# 2074.net
KiCad netlist of a schematic drawn in Altium Designer
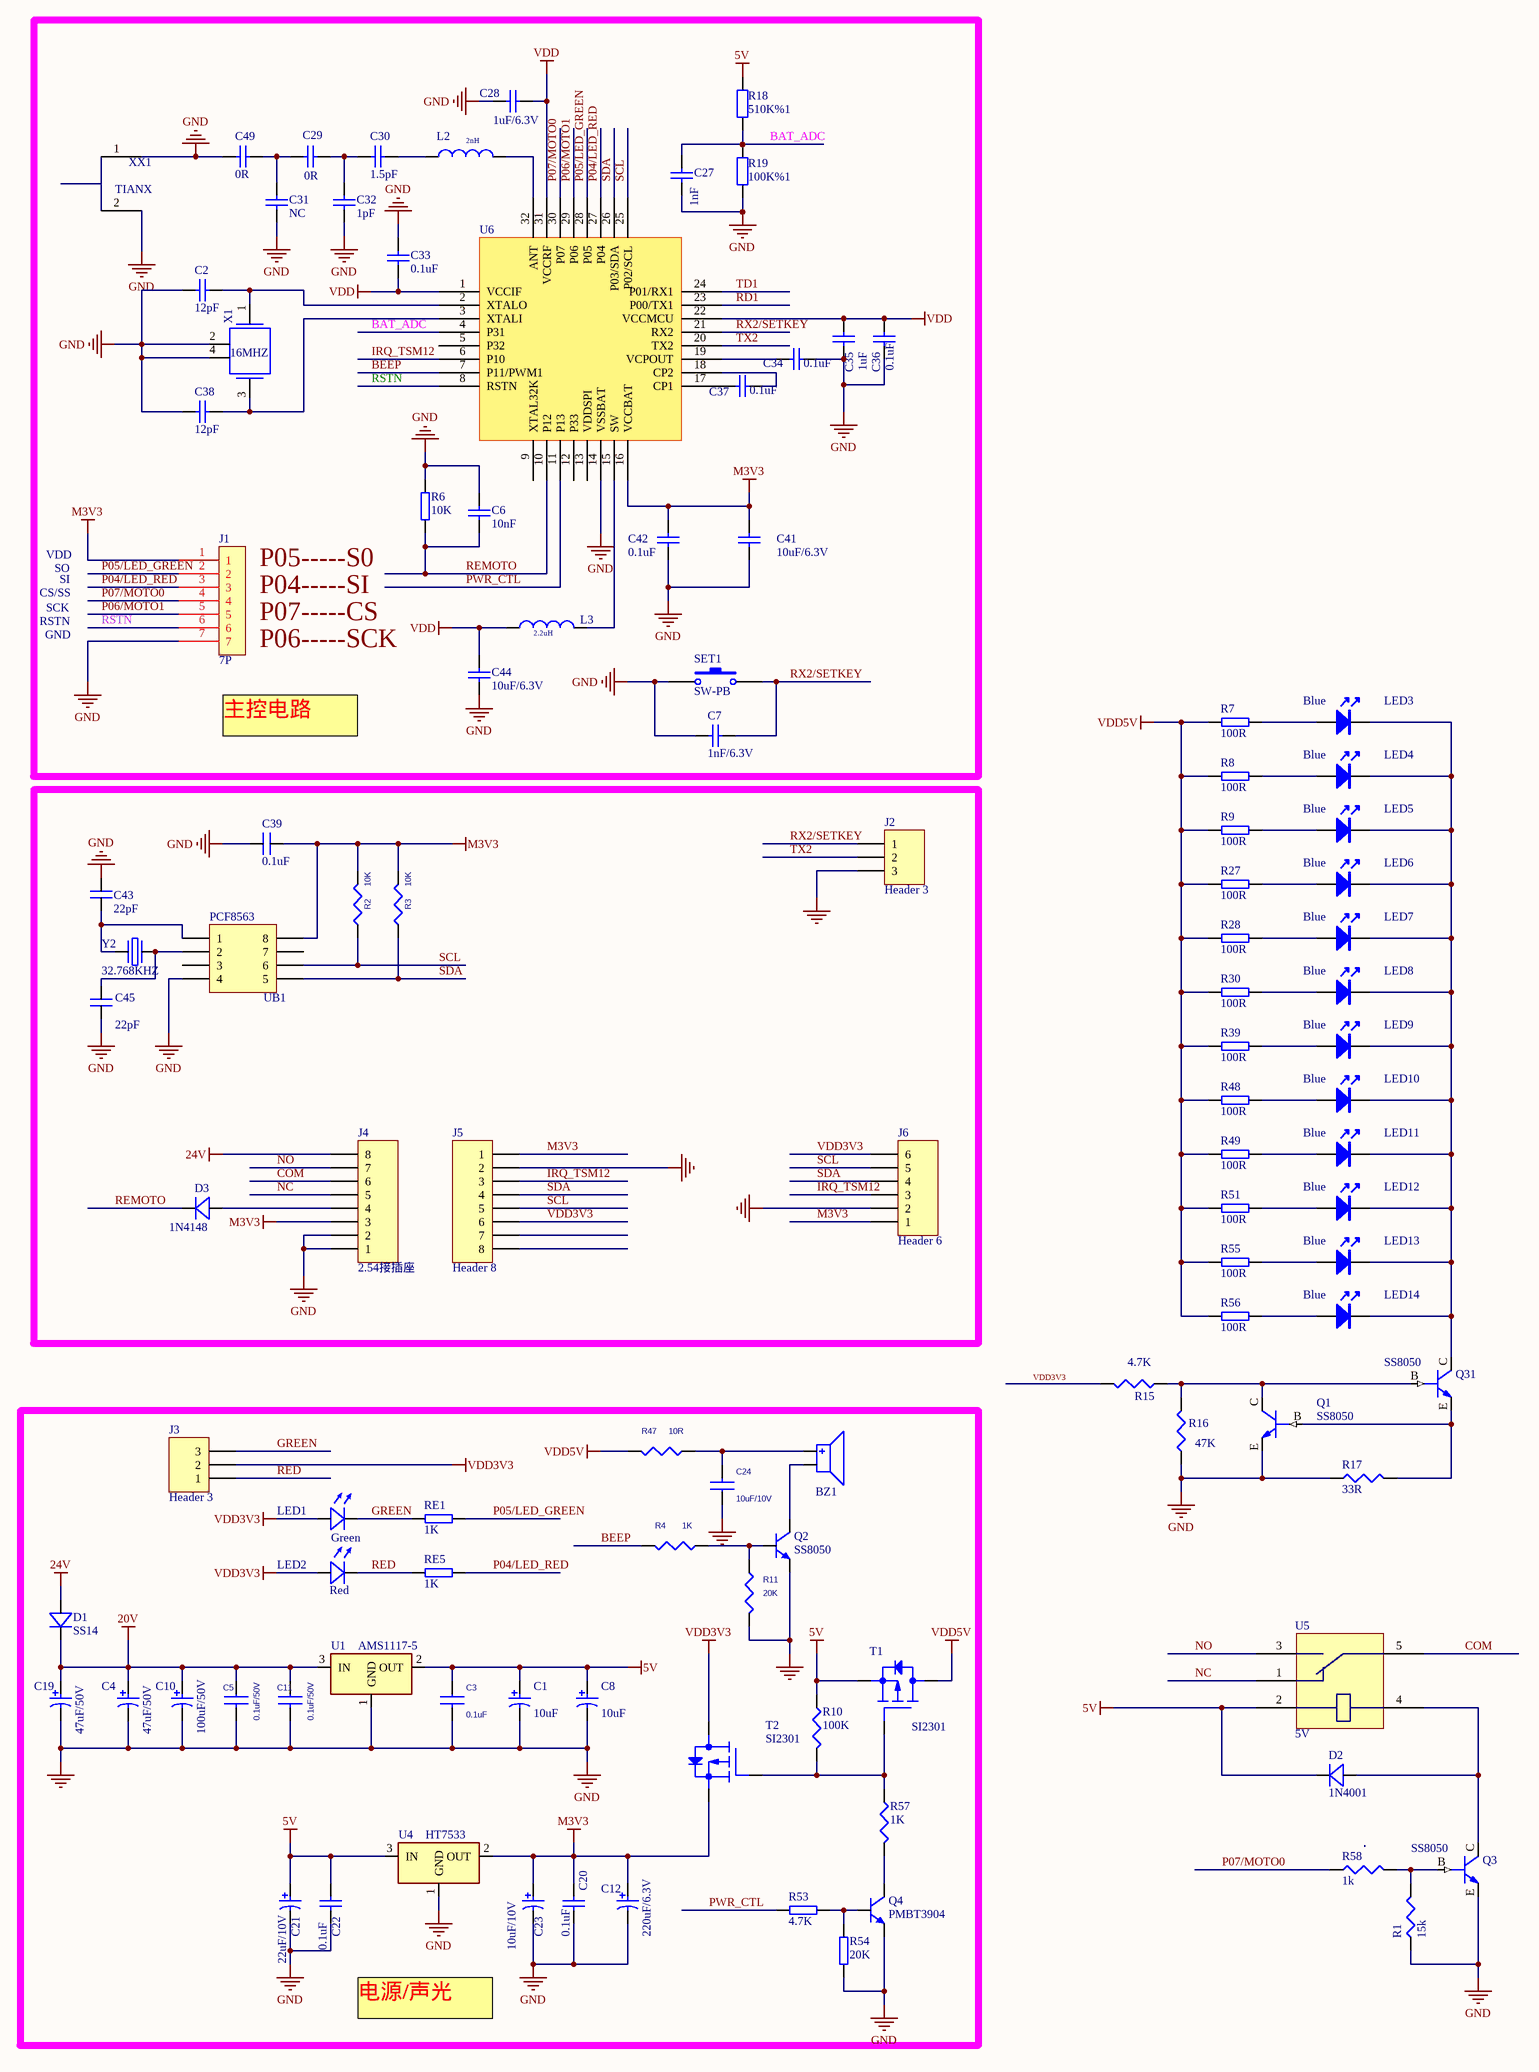
[diagram p0: 天地通门禁2074.SchDoc]

(export (version "E")
  (design (tool "Eeschema 10.0.6"))
  (components
    (comp (ref "BZ1")
      (value "BUZZER")
      (footprint "BUZZ_EN")
      (description "Buzzer")
      (libsource (lib "MyLibrary") (part "BUZZER"))
    )
    (comp (ref "C1")
      (value "10uF")
      (footprint "R6.3*5.8")
      (description "Capacitor, tolerance ±20%")
      (libsource (lib "MySchLib") (part "CAP-P"))
    )
    (comp (ref "C2")
      (value "12pF")
      (footprint "0603C")
      (description "Capacitor")
      (fields (field (name "PUBLISHER") "Altium Limited"))
      (libsource (lib "MySchlib") (part "Cap"))
    )
    (comp (ref "C3") (value "0.1uF") (footprint "0603C") (libsource (lib "*") (part "CAP NP")))
    (comp (ref "C4")
      (value "47uF/50V")
      (footprint "R6.3*7.7")
      (description "Capacitor, tolerance ±20%")
      (libsource (lib "MySchLib") (part "CAP-P"))
    )
    (comp (ref "C5") (value "0.1uF/50V") (footprint "0805C") (libsource (lib "*") (part "CAP NP")))
    (comp (ref "C6")
      (value "10nF")
      (footprint "0603C")
      (description "Capacitor")
      (fields (field (name "PUBLISHER") "Altium Limited"))
      (libsource (lib "MySchlib") (part "Cap"))
    )
    (comp (ref "C7")
      (value "1nF/6.3V")
      (footprint "0603C")
      (description "Capacitor")
      (fields (field (name "PUBLISHER") "Altium Limited"))
      (libsource (lib "MySchlib") (part "Cap"))
    )
    (comp (ref "C8")
      (value "10uF")
      (footprint "0805C")
      (description "Capacitor, tolerance ±20%")
      (libsource (lib "MySchLib") (part "CAP-P"))
    )
    (comp (ref "C10")
      (value "100uF/50V")
      (footprint "R6.3*7.7")
      (description "Capacitor, tolerance ±20%")
      (libsource (lib "MySchLib") (part "CAP-P"))
    )
    (comp (ref "C11") (value "0.1uF/50V") (footprint "0805C") (libsource (lib "*") (part "CAP NP")))
    (comp (ref "C12")
      (value "220uF/6.3V")
      (footprint "R6.3*5.8")
      (description "Capacitor, tolerance ±20%")
      (libsource (lib "MySchLib") (part "CAP-P"))
    )
    (comp (ref "C19")
      (value "47uF/50V")
      (footprint "R6.3*7.7")
      (description "Capacitor, tolerance ±20%")
      (libsource (lib "MySchLib") (part "CAP-P"))
    )
    (comp (ref "C20")
      (value "0.1uF")
      (footprint "0603C")
      (description "Capacitor, Ceramic")
      (fields (field (name "TOLERANCE") "5 %"))
      (libsource (lib "MyLibrary") (part "CAP-NP"))
    )
    (comp (ref "C21")
      (value "22uF/10V")
      (footprint "0805C")
      (description "Capacitor, tolerance ±20%")
      (libsource (lib "MySchLib") (part "CAP-P"))
    )
    (comp (ref "C22")
      (value "0.1uF")
      (footprint "0603C")
      (description "Capacitor, Ceramic")
      (fields (field (name "TOLERANCE") "5 %"))
      (libsource (lib "MyLibrary") (part "CAP-NP"))
    )
    (comp (ref "C23")
      (value "10uF/10V")
      (footprint "0805C")
      (description "Capacitor, tolerance ±20%")
      (libsource (lib "MySchLib") (part "CAP-P"))
    )
    (comp (ref "C24") (value "10uF/10V") (footprint "0805C") (libsource (lib "*") (part "C_0_Dup1")))
    (comp (ref "C27")
      (value "1nF")
      (footprint "0603C")
      (description "Capacitor, Ceramic")
      (fields (field (name "TOLERANCE") "5 %"))
      (libsource (lib "MyLibrary") (part "CAP-NP"))
    )
    (comp (ref "C28")
      (value "1uF/6.3V")
      (footprint "0603C")
      (description "Capacitor")
      (fields (field (name "PUBLISHER") "Altium Limited"))
      (libsource (lib "MySchlib") (part "Cap"))
    )
    (comp (ref "C29")
      (value "0R")
      (footprint "0603C")
      (description "Capacitor")
      (fields (field (name "PUBLISHER") "Altium Limited"))
      (libsource (lib "MySchlib") (part "Cap"))
    )
    (comp (ref "C30")
      (value "1.5pF")
      (footprint "0603C")
      (description "Capacitor")
      (fields (field (name "PUBLISHER") "Altium Limited"))
      (libsource (lib "MySchlib") (part "Cap"))
    )
    (comp (ref "C31")
      (value "NC")
      (footprint "0603C")
      (description "Capacitor")
      (fields (field (name "PUBLISHER") "Altium Limited"))
      (libsource (lib "MySchlib") (part "Cap"))
    )
    (comp (ref "C32")
      (value "1pF")
      (footprint "0603C")
      (description "Capacitor")
      (fields (field (name "PUBLISHER") "Altium Limited"))
      (libsource (lib "MySchlib") (part "Cap"))
    )
    (comp (ref "C33")
      (value "0.1uF")
      (footprint "0603C")
      (description "Capacitor")
      (fields (field (name "PUBLISHER") "Altium Limited"))
      (libsource (lib "MySchlib") (part "Cap"))
    )
    (comp (ref "C34")
      (value "0.1uF")
      (footprint "0603C")
      (description "Capacitor")
      (fields (field (name "PUBLISHER") "Altium Limited"))
      (libsource (lib "MySchlib") (part "Cap"))
    )
    (comp (ref "C35")
      (value "1uF")
      (footprint "0603C")
      (description "Capacitor")
      (fields (field (name "PUBLISHER") "Altium Limited"))
      (libsource (lib "MySchlib") (part "Cap"))
    )
    (comp (ref "C36")
      (value "0.1uF")
      (footprint "0603C")
      (description "Capacitor")
      (fields (field (name "PUBLISHER") "Altium Limited"))
      (libsource (lib "MySchlib") (part "Cap"))
    )
    (comp (ref "C37")
      (value "0.1uF")
      (footprint "0603C")
      (description "Capacitor")
      (fields (field (name "PUBLISHER") "Altium Limited"))
      (libsource (lib "MySchlib") (part "Cap"))
    )
    (comp (ref "C38")
      (value "12pF")
      (footprint "0603C")
      (description "Capacitor")
      (fields (field (name "PUBLISHER") "Altium Limited"))
      (libsource (lib "MySchlib") (part "Cap"))
    )
    (comp (ref "C39") (value "0.1uF") (footprint "0603C") (libsource (lib "自建元件库") (part "C")))
    (comp (ref "C41")
      (value "10uF/6.3V")
      (footprint "0603C")
      (description "Capacitor")
      (fields (field (name "PUBLISHER") "Altium Limited"))
      (libsource (lib "MySchlib") (part "Cap"))
    )
    (comp (ref "C42")
      (value "0.1uF")
      (footprint "0603C")
      (description "Capacitor")
      (fields (field (name "PUBLISHER") "Altium Limited"))
      (libsource (lib "MySchlib") (part "Cap"))
    )
    (comp (ref "C43") (value "22pF") (footprint "0603C") (libsource (lib "自建元件库") (part "C")))
    (comp (ref "C44")
      (value "10uF/6.3V")
      (footprint "0603C")
      (description "Capacitor")
      (fields (field (name "PUBLISHER") "Altium Limited"))
      (libsource (lib "MySchlib") (part "Cap"))
    )
    (comp (ref "C45") (value "22pF") (footprint "0603C") (libsource (lib "自建元件库") (part "C")))
    (comp (ref "C49")
      (value "0R")
      (footprint "0603C")
      (description "Capacitor")
      (fields (field (name "PUBLISHER") "Altium Limited"))
      (libsource (lib "MySchlib") (part "Cap"))
    )
    (comp (ref "D1") (value "SS14") (footprint "DO-214AA") (libsource (lib "MySch") (part "D")))
    (comp (ref "D2") (value "1N4001") (footprint "M7") (libsource (lib "") (part "D_1")))
    (comp (ref "D3") (value "1N4148") (footprint "SOD-323") (libsource (lib "MySch") (part "D")))
    (comp (ref "J1") (value "7P") (footprint "7P-2.0MM") (libsource (lib "保险箱STM32") (part "7P")))
    (comp (ref "J2")
      (value "Header 3")
      (footprint "3P-2.0MM")
      (description "Header, 3-Pin")
      (fields (field (name "PUBLISHER") "Altium Limited"))
      (libsource (lib "Miscellaneous Connectors") (part "Header 3"))
    )
    (comp (ref "J3")
      (value "Header 3")
      (footprint "3PIN-2.0")
      (description "Header, 3-Pin")
      (fields (field (name "PUBLISHER") "Altium Limited"))
      (libsource (lib "") (part "Header 3_1"))
    )
    (comp (ref "J4")
      (value "2.54接插座")
      (footprint "2.54螺丝接线座8P")
      (description "Header, 8-Pin")
      (fields (field (name "PUBLISHER") "Altium Limited"))
      (libsource (lib "Miscellaneous Connectors") (part "Header 8"))
    )
    (comp (ref "J5")
      (value "Header 8")
      (footprint "8P-1.25mm")
      (description "Header, 8-Pin")
      (fields (field (name "PUBLISHER") "Altium Limited"))
      (libsource (lib "") (part "Header 8_1"))
    )
    (comp (ref "J6")
      (value "Header 6")
      (footprint "6P-1.25mm")
      (description "Header, 6-Pin")
      (fields (field (name "PUBLISHER") "Altium Limited"))
      (libsource (lib "Miscellaneous Connectors") (part "Header 6"))
    )
    (comp (ref "L2")
      (value "2nH")
      (footprint "0603L")
      (description "Power Inductor, 4.7uH, 0.7A, 260mR DCR")
      (fields
        (field (name "XMOS PART NUMBER") "E-09-0011")
        (field (name "MANUFACTURER") "Taiyo Yuden")
        (field (name "PART CREATOR") "JG")
        (field (name "APPROVED") "NO")
      )
      (libsource (lib "MySchlib") (part "INDUCTOR"))
    )
    (comp (ref "L3")
      (value "2.2uH")
      (footprint "0603L")
      (description "Power Inductor, 4.7uH, 0.7A, 260mR DCR")
      (fields
        (field (name "XMOS PART NUMBER") "E-09-0011")
        (field (name "MANUFACTURER") "Taiyo Yuden")
        (field (name "PART CREATOR") "JG")
        (field (name "APPROVED") "NO")
      )
      (libsource (lib "MySchlib") (part "INDUCTOR"))
    )
    (comp (ref "LED1") (value "Green") (footprint "0805LED") (libsource (lib "MyLibrary") (part "LED")))
    (comp (ref "LED2") (value "Red") (footprint "0805LED") (libsource (lib "MyLibrary") (part "LED")))
    (comp (ref "LED3") (value "Blue") (footprint "0805LED") (libsource (lib "*") (part "LED")))
    (comp (ref "LED4") (value "Blue") (footprint "0805LED") (libsource (lib "*") (part "LED")))
    (comp (ref "LED5") (value "Blue") (footprint "0805LED") (libsource (lib "*") (part "LED")))
    (comp (ref "LED6") (value "Blue") (footprint "0805LED") (libsource (lib "*") (part "LED")))
    (comp (ref "LED7") (value "Blue") (footprint "0805LED") (libsource (lib "*") (part "LED")))
    (comp (ref "LED8") (value "Blue") (footprint "0805LED") (libsource (lib "*") (part "LED")))
    (comp (ref "LED9") (value "Blue") (footprint "0805LED") (libsource (lib "*") (part "LED")))
    (comp (ref "LED10") (value "Blue") (footprint "0805LED") (libsource (lib "*") (part "LED")))
    (comp (ref "LED11") (value "Blue") (footprint "0805LED") (libsource (lib "*") (part "LED")))
    (comp (ref "LED12") (value "Blue") (footprint "0805LED") (libsource (lib "*") (part "LED")))
    (comp (ref "LED13") (value "Blue") (footprint "0805LED") (libsource (lib "*") (part "LED")))
    (comp (ref "LED14") (value "Blue") (footprint "0805LED") (libsource (lib "*") (part "LED")))
    (comp (ref "Q1") (value "SS8050") (footprint "SOT-23 - BCE") (libsource (lib "*") (part "PMBT3904")))
    (comp (ref "Q2")
      (value "SS8050")
      (footprint "SOT-23-3L")
      (description "Bipolar Junction Transistor")
      (libsource (lib "MyLibrary") (part "NPN_BJT"))
    )
    (comp (ref "Q3") (value "SS8050") (footprint "SOT-23 - BCE") (libsource (lib "*") (part "PMBT3904")))
    (comp (ref "Q4")
      (value "PMBT3904")
      (footprint "SOT-23-3L")
      (description "Bipolar Junction Transistor")
      (libsource (lib "MyLibrary") (part "NPN_BJT"))
    )
    (comp (ref "Q31") (value "SS8050") (footprint "SOT-23 - BCE") (libsource (lib "*") (part "PMBT3904")))
    (comp (ref "R1") (value "15k") (footprint "0603R") (libsource (lib "*") (part "R")))
    (comp (ref "R2") (value "10K") (footprint "0603R") (libsource (lib "*") (part "RES")))
    (comp (ref "R3") (value "10K") (footprint "0603R") (libsource (lib "*") (part "RES")))
    (comp (ref "R4") (value "1K") (footprint "0603R") (libsource (lib "*") (part "R_Dup1")))
    (comp (ref "R6") (value "10K") (footprint "0603R") (libsource (lib "MySch") (part "R")))
    (comp (ref "R7") (value "100R") (footprint "0603R") (libsource (lib "MySch") (part "R")))
    (comp (ref "R8") (value "100R") (footprint "0603R") (libsource (lib "MySch") (part "R")))
    (comp (ref "R9") (value "100R") (footprint "0603R") (libsource (lib "MySch") (part "R")))
    (comp (ref "R10") (value "100K") (footprint "0603R") (libsource (lib "*") (part "R")))
    (comp (ref "R11") (value "20K") (footprint "0603R") (libsource (lib "*") (part "R_Dup1")))
    (comp (ref "R15") (value "4.7K") (footprint "0603R") (libsource (lib "*") (part "R")))
    (comp (ref "R16") (value "47K") (footprint "0603R") (libsource (lib "*") (part "R")))
    (comp (ref "R17") (value "33R") (footprint "0603R") (libsource (lib "*") (part "R")))
    (comp (ref "R18")
      (value "510K%1")
      (footprint "0603R")
      (description "Resistor")
      (libsource (lib "MyLibrary") (part "Res2"))
    )
    (comp (ref "R19")
      (value "100K%1")
      (footprint "0603R")
      (description "Resistor")
      (libsource (lib "MyLibrary") (part "Res2"))
    )
    (comp (ref "R27") (value "100R") (footprint "0603R") (libsource (lib "MySch") (part "R")))
    (comp (ref "R28") (value "100R") (footprint "0603R") (libsource (lib "MySch") (part "R")))
    (comp (ref "R30") (value "100R") (footprint "0603R") (libsource (lib "MySch") (part "R")))
    (comp (ref "R39") (value "100R") (footprint "0603R") (libsource (lib "MySch") (part "R")))
    (comp (ref "R47") (value "10R") (footprint "0603R") (libsource (lib "*") (part "R_Dup1")))
    (comp (ref "R48") (value "100R") (footprint "0603R") (libsource (lib "MySch") (part "R")))
    (comp (ref "R49") (value "100R") (footprint "0603R") (libsource (lib "MySch") (part "R")))
    (comp (ref "R51") (value "100R") (footprint "0603R") (libsource (lib "MySch") (part "R")))
    (comp (ref "R53") (value "4.7K") (footprint "0603R") (libsource (lib "MySch") (part "R")))
    (comp (ref "R54") (value "20K") (footprint "0603R") (libsource (lib "MySch") (part "R")))
    (comp (ref "R55") (value "100R") (footprint "0603R") (libsource (lib "MySch") (part "R")))
    (comp (ref "R56") (value "100R") (footprint "0603R") (libsource (lib "MySch") (part "R")))
    (comp (ref "R57") (value "1K") (footprint "0603R") (libsource (lib "*") (part "R")))
    (comp (ref "R58") (value "1k") (footprint "0603R") (libsource (lib "*") (part "R")))
    (comp (ref "RE1") (value "1K") (footprint "0603R") (libsource (lib "MySch") (part "R")))
    (comp (ref "RE5") (value "1K") (footprint "0603R") (libsource (lib "MySch") (part "R")))
    (comp (ref "SET1")
      (value "SW-PB")
      (footprint "KEY-S")
      (description "Switch")
      (fields (field (name "PUBLISHER") "Altium Limited"))
      (libsource (lib "Miscellaneous Devices") (part "SW-PB"))
    )
    (comp (ref "T1")
      (value "SI2301")
      (footprint "SOT-23 - GDS")
      (libsource (lib "*") (part "PWRMOSFET_EP_DGS_0"))
    )
    (comp (ref "T2")
      (value "SI2301")
      (footprint "SOT-23 - GDS")
      (libsource (lib "*") (part "PWRMOSFET_EP_DGS_0"))
    )
    (comp (ref "U1") (value "AMS1117-5") (footprint "SOT223_M") (libsource (lib "*") (part "XC6206P302M")))
    (comp (ref "U4") (value "HT7533") (footprint "SOT-23-3L") (libsource (lib "*") (part "XC6206P302M")))
    (comp (ref "U5") (value "5V") (footprint "继电器1x") (libsource (lib "MYSchlib") (part "OMRON_G8P-1A4P")))
    (comp (ref "U6")
      (value "BK3431Q")
      (footprint "QFN32_4*4*0.4")
      (libsource (lib "BK3431") (part "BK3431Q"))
    )
    (comp (ref "UB1") (value "PCF8563") (footprint "SOP8") (libsource (lib "MySch") (part "IC8")))
    (comp (ref "X1")
      (value "16MHZ")
      (footprint "XTAL3225")
      (fields
        (field (name "XMOS PART NUMBER") "E-07-0030")
        (field (name "MANUFACTURER") "Abracon")
        (field (name "MANUFACTURER PART NUMBER") "ABLS-24.000MHz-B4")
        (field (name "PART CREATOR") "JG")
        (field (name "APPROVED") "NO")
      )
      (libsource (lib "MySchlib") (part "OSC"))
    )
    (comp (ref "XX1")
      (value "TIANX")
      (footprint "BT_NAMI_1")
      (libsource (lib "885阿里云PCB_Project1") (part "TIANX"))
    )
    (comp (ref "Y2") (value "32.768KHZ") (footprint "晶振-9") (libsource (lib "MySch") (part "晶振")))
  )
  (nets
    (net (code "1") (name "/BAT_ADC") (class "Default")
      (node (ref "C27") (pin "2") (pinfunction "2_2") (pintype "passive"))
      (node (ref "R18") (pin "2") (pinfunction "2_2") (pintype "passive"))
      (node (ref "R19") (pin "1") (pinfunction "1_1") (pintype "passive"))
      (node (ref "U6") (pin "4") (pinfunction "P31_4") (pintype "passive"))
    )
    (net (code "2") (name "/BEEP") (class "Default")
      (node (ref "R4") (pin "2") (pinfunction "2_2") (pintype "passive"))
      (node (ref "U6") (pin "7") (pinfunction "P11/PWM1_7") (pintype "passive"))
    )
    (net (code "3") (name "/COM") (class "Default")
      (node (ref "J4") (pin "6") (pinfunction "6_6") (pintype "passive"))
      (node (ref "U5") (pin "5") (pinfunction "5_5") (pintype "passive"))
    )
    (net (code "4") (name "/GREEN") (class "Default")
      (node (ref "J3") (pin "3") (pinfunction "3_3") (pintype "passive"))
      (node (ref "LED1") (pin "2") (pinfunction "K_2") (pintype "passive"))
      (node (ref "RE1") (pin "1") (pintype "passive"))
    )
    (net (code "5") (name "/IRQ_TSM12") (class "Default")
      (node (ref "J5") (pin "3") (pinfunction "3_3") (pintype "passive"))
      (node (ref "J6") (pin "3") (pinfunction "3_3") (pintype "passive"))
      (node (ref "U6") (pin "6") (pinfunction "P10_6") (pintype "passive"))
    )
    (net (code "6") (name "/NC") (class "Default")
      (node (ref "J4") (pin "5") (pinfunction "5_5") (pintype "passive"))
      (node (ref "U5") (pin "1") (pinfunction "1_1") (pintype "passive"))
    )
    (net (code "7") (name "/NO") (class "Default")
      (node (ref "J4") (pin "7") (pinfunction "7_7") (pintype "passive"))
      (node (ref "U5") (pin "3") (pinfunction "3_3") (pintype "passive"))
    )
    (net (code "8") (name "/P04{slash}LED_RED") (class "Default")
      (node (ref "J1") (pin "3") (pinfunction "3_3") (pintype "passive"))
      (node (ref "RE5") (pin "2") (pintype "passive"))
      (node (ref "U6") (pin "27") (pinfunction "P04_27") (pintype "passive"))
    )
    (net (code "9") (name "/P05{slash}LED_GREEN") (class "Default")
      (node (ref "J1") (pin "2") (pinfunction "2_2") (pintype "passive"))
      (node (ref "RE1") (pin "2") (pintype "passive"))
      (node (ref "U6") (pin "28") (pinfunction "P05_28") (pintype "passive"))
    )
    (net (code "10") (name "/P06{slash}MOTO1") (class "Default")
      (node (ref "J1") (pin "5") (pinfunction "5_5") (pintype "passive"))
      (node (ref "U6") (pin "29") (pinfunction "P06_29") (pintype "passive"))
    )
    (net (code "11") (name "/P07{slash}MOTO0") (class "Default")
      (node (ref "J1") (pin "4") (pinfunction "4_4") (pintype "passive"))
      (node (ref "R58") (pin "1") (pinfunction "1_1") (pintype "passive"))
      (node (ref "U6") (pin "30") (pinfunction "P07_30") (pintype "passive"))
    )
    (net (code "12") (name "/PWR_CTL") (class "Default")
      (node (ref "R53") (pin "1") (pintype "passive"))
      (node (ref "U6") (pin "11") (pinfunction "P13_11") (pintype "passive"))
    )
    (net (code "13") (name "/RD1") (class "Default")
      (node (ref "U6") (pin "23") (pinfunction "P00/TX1_23") (pintype "passive"))
    )
    (net (code "14") (name "/RED") (class "Default")
      (node (ref "J3") (pin "1") (pinfunction "1_1") (pintype "passive"))
      (node (ref "LED2") (pin "2") (pinfunction "K_2") (pintype "passive"))
      (node (ref "RE5") (pin "1") (pintype "passive"))
    )
    (net (code "15") (name "/REMOTO") (class "Default")
      (node (ref "C6") (pin "2") (pinfunction "2_2") (pintype "passive"))
      (node (ref "D3") (pin "2") (pinfunction "K_2") (pintype "passive"))
      (node (ref "R6") (pin "1") (pintype "passive"))
      (node (ref "U6") (pin "10") (pinfunction "P12_10") (pintype "passive"))
    )
    (net (code "16") (name "/RSTN") (class "Default")
      (node (ref "J1") (pin "6") (pinfunction "6_6") (pintype "passive"))
      (node (ref "U6") (pin "8") (pinfunction "RSTN_8") (pintype "passive"))
    )
    (net (code "17") (name "/RX2{slash}SETKEY") (class "Default")
      (node (ref "C7") (pin "1") (pinfunction "1_1") (pintype "passive"))
      (node (ref "J2") (pin "1") (pinfunction "1_1") (pintype "passive"))
      (node (ref "SET1") (pin "2") (pinfunction "2_2") (pintype "passive"))
      (node (ref "U6") (pin "21") (pinfunction "RX2_21") (pintype "passive"))
    )
    (net (code "18") (name "/SCL") (class "Default")
      (node (ref "J5") (pin "5") (pinfunction "5_5") (pintype "passive"))
      (node (ref "J6") (pin "5") (pinfunction "5_5") (pintype "passive"))
      (node (ref "R2") (pin "2") (pinfunction "2_2") (pintype "passive"))
      (node (ref "U6") (pin "25") (pinfunction "P02/SCL_25") (pintype "passive"))
      (node (ref "UB1") (pin "6") (pinfunction "6_6") (pintype "passive"))
    )
    (net (code "19") (name "/SDA") (class "Default")
      (node (ref "J5") (pin "4") (pinfunction "4_4") (pintype "passive"))
      (node (ref "J6") (pin "4") (pinfunction "4_4") (pintype "passive"))
      (node (ref "R3") (pin "2") (pinfunction "2_2") (pintype "passive"))
      (node (ref "U6") (pin "26") (pinfunction "P03/SDA_26") (pintype "passive"))
      (node (ref "UB1") (pin "5") (pinfunction "5_5") (pintype "passive"))
    )
    (net (code "20") (name "/TD1") (class "Default")
      (node (ref "U6") (pin "24") (pinfunction "P01/RX1_24") (pintype "passive"))
    )
    (net (code "21") (name "/TX2") (class "Default")
      (node (ref "J2") (pin "2") (pinfunction "2_2") (pintype "passive"))
      (node (ref "U6") (pin "20") (pinfunction "TX2_20") (pintype "passive"))
    )
    (net (code "22") (name "5V") (class "Default")
      (node (ref "C1") (pin "1") (pinfunction "1_1") (pintype "passive"))
      (node (ref "C21") (pin "1") (pinfunction "1_1") (pintype "passive"))
      (node (ref "C22") (pin "1") (pinfunction "1_1") (pintype "passive"))
      (node (ref "C3") (pin "1") (pinfunction "1_1") (pintype "passive"))
      (node (ref "C8") (pin "1") (pinfunction "1_1") (pintype "passive"))
      (node (ref "D2") (pin "K") (pinfunction "A_K") (pintype "passive"))
      (node (ref "R10") (pin "1") (pinfunction "1_1") (pintype "passive"))
      (node (ref "R18") (pin "1") (pinfunction "1_1") (pintype "passive"))
      (node (ref "T1") (pin "S") (pinfunction "SOURCE_S") (pintype "passive"))
      (node (ref "U1") (pin "2") (pinfunction "OUT_2") (pintype "passive"))
      (node (ref "U4") (pin "3") (pinfunction "IN_3") (pintype "passive"))
      (node (ref "U5") (pin "2") (pinfunction "2_2") (pintype "passive"))
    )
    (net (code "23") (name "20V") (class "Default")
      (node (ref "C10") (pin "1") (pinfunction "1_1") (pintype "passive"))
      (node (ref "C11") (pin "1") (pinfunction "1_1") (pintype "passive"))
      (node (ref "C19") (pin "1") (pinfunction "1_1") (pintype "passive"))
      (node (ref "C4") (pin "1") (pinfunction "1_1") (pintype "passive"))
      (node (ref "C5") (pin "1") (pinfunction "1_1") (pintype "passive"))
      (node (ref "D1") (pin "2") (pinfunction "K_2") (pintype "passive"))
      (node (ref "U1") (pin "3") (pinfunction "IN_3") (pintype "passive"))
    )
    (net (code "24") (name "24V") (class "Default")
      (node (ref "D1") (pin "1") (pinfunction "A_1") (pintype "passive"))
      (node (ref "J4") (pin "8") (pinfunction "8_8") (pintype "passive"))
    )
    (net (code "25") (name "GND") (class "Default")
      (node (ref "C1") (pin "2") (pinfunction "2_2") (pintype "passive"))
      (node (ref "C10") (pin "2") (pinfunction "2_2") (pintype "passive"))
      (node (ref "C11") (pin "2") (pinfunction "2_2") (pintype "passive"))
      (node (ref "C12") (pin "2") (pinfunction "2_2") (pintype "passive"))
      (node (ref "C19") (pin "2") (pinfunction "2_2") (pintype "passive"))
      (node (ref "C2") (pin "1") (pinfunction "1_1") (pintype "passive"))
      (node (ref "C20") (pin "2") (pinfunction "2_2") (pintype "passive"))
      (node (ref "C21") (pin "2") (pinfunction "2_2") (pintype "passive"))
      (node (ref "C22") (pin "2") (pinfunction "2_2") (pintype "passive"))
      (node (ref "C23") (pin "2") (pinfunction "2_2") (pintype "passive"))
      (node (ref "C24") (pin "1") (pinfunction "1_1") (pintype "passive"))
      (node (ref "C27") (pin "1") (pinfunction "1_1") (pintype "passive"))
      (node (ref "C28") (pin "1") (pinfunction "1_1") (pintype "passive"))
      (node (ref "C3") (pin "2") (pinfunction "2_2") (pintype "passive"))
      (node (ref "C31") (pin "2") (pinfunction "2_2") (pintype "passive"))
      (node (ref "C32") (pin "1") (pinfunction "1_1") (pintype "passive"))
      (node (ref "C33") (pin "1") (pinfunction "1_1") (pintype "passive"))
      (node (ref "C34") (pin "2") (pinfunction "2_2") (pintype "passive"))
      (node (ref "C35") (pin "1") (pinfunction "1_1") (pintype "passive"))
      (node (ref "C36") (pin "1") (pinfunction "1_1") (pintype "passive"))
      (node (ref "C38") (pin "1") (pinfunction "1_1") (pintype "passive"))
      (node (ref "C39") (pin "2") (pintype "passive"))
      (node (ref "C4") (pin "2") (pinfunction "2_2") (pintype "passive"))
      (node (ref "C41") (pin "2") (pinfunction "2_2") (pintype "passive"))
      (node (ref "C42") (pin "2") (pinfunction "2_2") (pintype "passive"))
      (node (ref "C43") (pin "2") (pintype "passive"))
      (node (ref "C44") (pin "1") (pinfunction "1_1") (pintype "passive"))
      (node (ref "C45") (pin "1") (pintype "passive"))
      (node (ref "C49") (pin "1") (pinfunction "1_1") (pintype "passive"))
      (node (ref "C5") (pin "2") (pinfunction "2_2") (pintype "passive"))
      (node (ref "C6") (pin "1") (pinfunction "1_1") (pintype "passive"))
      (node (ref "C7") (pin "2") (pinfunction "2_2") (pintype "passive"))
      (node (ref "C8") (pin "2") (pinfunction "2_2") (pintype "passive"))
      (node (ref "J1") (pin "7") (pinfunction "7_7") (pintype "passive"))
      (node (ref "J2") (pin "3") (pinfunction "3_3") (pintype "passive"))
      (node (ref "J4") (pin "1") (pinfunction "1_1") (pintype "passive"))
      (node (ref "J4") (pin "2") (pinfunction "2_2") (pintype "passive"))
      (node (ref "J5") (pin "2") (pinfunction "2_2") (pintype "passive"))
      (node (ref "J6") (pin "2") (pinfunction "2_2") (pintype "passive"))
      (node (ref "Q1") (pin "E") (pinfunction "EMITTER_E") (pintype "passive"))
      (node (ref "Q2") (pin "2") (pinfunction "2_2") (pintype "passive"))
      (node (ref "Q3") (pin "E") (pinfunction "EMITTER_E") (pintype "passive"))
      (node (ref "Q4") (pin "2") (pinfunction "2_2") (pintype "passive"))
      (node (ref "R1") (pin "1") (pinfunction "1_1") (pintype "passive"))
      (node (ref "R11") (pin "2") (pinfunction "2_2") (pintype "passive"))
      (node (ref "R16") (pin "1") (pinfunction "1_1") (pintype "passive"))
      (node (ref "R17") (pin "1") (pinfunction "1_1") (pintype "passive"))
      (node (ref "R19") (pin "2") (pinfunction "2_2") (pintype "passive"))
      (node (ref "R54") (pin "1") (pintype "passive"))
      (node (ref "R6") (pin "2") (pintype "passive"))
      (node (ref "SET1") (pin "1") (pinfunction "1_1") (pintype "passive"))
      (node (ref "U1") (pin "1") (pinfunction "GND_1") (pintype "passive"))
      (node (ref "U4") (pin "1") (pinfunction "GND_1") (pintype "passive"))
      (node (ref "U6") (pin "14") (pinfunction "VSSBAT_14") (pintype "passive"))
      (node (ref "UB1") (pin "4") (pinfunction "4_4") (pintype "passive"))
      (node (ref "X1") (pin "2") (pintype "passive"))
      (node (ref "X1") (pin "4") (pintype "passive"))
      (node (ref "XX1") (pin "1") (pinfunction "1_1") (pintype "passive"))
      (node (ref "XX1") (pin "2") (pinfunction "2_2") (pintype "passive"))
    )
    (net (code "26") (name "M3V3") (class "Default")
      (node (ref "C12") (pin "1") (pinfunction "1_1") (pintype "passive"))
      (node (ref "C20") (pin "1") (pinfunction "1_1") (pintype "passive"))
      (node (ref "C23") (pin "1") (pinfunction "1_1") (pintype "passive"))
      (node (ref "C39") (pin "1") (pintype "passive"))
      (node (ref "C41") (pin "1") (pinfunction "1_1") (pintype "passive"))
      (node (ref "C42") (pin "1") (pinfunction "1_1") (pintype "passive"))
      (node (ref "J1") (pin "1") (pinfunction "1_1") (pintype "passive"))
      (node (ref "J4") (pin "3") (pinfunction "3_3") (pintype "passive"))
      (node (ref "J5") (pin "1") (pinfunction "1_1") (pintype "passive"))
      (node (ref "J6") (pin "1") (pinfunction "1_1") (pintype "passive"))
      (node (ref "R2") (pin "1") (pinfunction "1_1") (pintype "passive"))
      (node (ref "R3") (pin "1") (pinfunction "1_1") (pintype "passive"))
      (node (ref "T2") (pin "S") (pinfunction "SOURCE_S") (pintype "passive"))
      (node (ref "U4") (pin "2") (pinfunction "OUT_2") (pintype "passive"))
      (node (ref "U6") (pin "16") (pinfunction "VCCBAT_16") (pintype "passive"))
      (node (ref "UB1") (pin "8") (pinfunction "8_8") (pintype "passive"))
    )
    (net (code "27") (name "Net-(BZ1-Pad1)") (class "Default")
      (node (ref "BZ1") (pin "1") (pintype "passive"))
      (node (ref "C24") (pin "2") (pinfunction "2_2") (pintype "passive"))
      (node (ref "R47") (pin "1") (pinfunction "1_1") (pintype "passive"))
    )
    (net (code "28") (name "Net-(BZ1-Pad2)") (class "Default")
      (node (ref "BZ1") (pin "2") (pintype "passive"))
      (node (ref "Q2") (pin "3") (pinfunction "3_3") (pintype "passive"))
    )
    (net (code "29") (name "Net-(C29-Pad1)") (class "Default")
      (node (ref "C29") (pin "1") (pinfunction "1_1") (pintype "passive"))
      (node (ref "C31") (pin "1") (pinfunction "1_1") (pintype "passive"))
      (node (ref "C49") (pin "2") (pinfunction "2_2") (pintype "passive"))
    )
    (net (code "30") (name "Net-(C29-Pad2)") (class "Default")
      (node (ref "C29") (pin "2") (pinfunction "2_2") (pintype "passive"))
      (node (ref "C30") (pin "2") (pinfunction "2_2") (pintype "passive"))
      (node (ref "C32") (pin "2") (pinfunction "2_2") (pintype "passive"))
    )
    (net (code "31") (name "Net-(C43-Pad1)") (class "Default")
      (node (ref "C43") (pin "1") (pintype "passive"))
      (node (ref "UB1") (pin "1") (pinfunction "1_1") (pintype "passive"))
      (node (ref "Y2") (pin "2") (pintype "passive"))
    )
    (net (code "32") (name "Net-(C45-Pad2)") (class "Default")
      (node (ref "C45") (pin "2") (pintype "passive"))
      (node (ref "UB1") (pin "2") (pinfunction "2_2") (pintype "passive"))
      (node (ref "Y2") (pin "1") (pintype "passive"))
    )
    (net (code "33") (name "Net-(D2-K)") (class "Default")
      (node (ref "D2") (pin "A") (pinfunction "K_A") (pintype "passive"))
      (node (ref "Q3") (pin "C") (pinfunction "COLLECTOR_C") (pintype "passive"))
      (node (ref "U5") (pin "4") (pinfunction "4_4") (pintype "passive"))
    )
    (net (code "34") (name "Net-(D3-A)") (class "Default")
      (node (ref "D3") (pin "1") (pinfunction "A_1") (pintype "passive"))
      (node (ref "J4") (pin "4") (pinfunction "4_4") (pintype "passive"))
    )
    (net (code "35") (name "Net-(L2-P1)") (class "Default")
      (node (ref "C30") (pin "1") (pinfunction "1_1") (pintype "passive"))
      (node (ref "L2") (pin "1") (pinfunction "P1_1") (pintype "passive"))
    )
    (net (code "36") (name "Net-(L2-P2)") (class "Default")
      (node (ref "L2") (pin "2") (pinfunction "P2_2") (pintype "passive"))
      (node (ref "U6") (pin "32") (pinfunction "ANT_32") (pintype "passive"))
    )
    (net (code "37") (name "Net-(L3-P2)") (class "Default")
      (node (ref "L3") (pin "2") (pinfunction "P2_2") (pintype "passive"))
      (node (ref "U6") (pin "15") (pinfunction "SW_15") (pintype "passive"))
    )
    (net (code "38") (name "Net-(LED3-Pad1)") (class "Default")
      (node (ref "LED3") (pin "1") (pinfunction "1_1") (pintype "passive"))
      (node (ref "R7") (pin "2") (pintype "passive"))
    )
    (net (code "39") (name "Net-(LED4-Pad1)") (class "Default")
      (node (ref "LED4") (pin "1") (pinfunction "1_1") (pintype "passive"))
      (node (ref "R8") (pin "2") (pintype "passive"))
    )
    (net (code "40") (name "Net-(LED5-Pad1)") (class "Default")
      (node (ref "LED5") (pin "1") (pinfunction "1_1") (pintype "passive"))
      (node (ref "R9") (pin "2") (pintype "passive"))
    )
    (net (code "41") (name "Net-(LED6-Pad1)") (class "Default")
      (node (ref "LED6") (pin "1") (pinfunction "1_1") (pintype "passive"))
      (node (ref "R27") (pin "2") (pintype "passive"))
    )
    (net (code "42") (name "Net-(LED7-Pad1)") (class "Default")
      (node (ref "LED7") (pin "1") (pinfunction "1_1") (pintype "passive"))
      (node (ref "R28") (pin "2") (pintype "passive"))
    )
    (net (code "43") (name "Net-(LED8-Pad1)") (class "Default")
      (node (ref "LED8") (pin "1") (pinfunction "1_1") (pintype "passive"))
      (node (ref "R30") (pin "2") (pintype "passive"))
    )
    (net (code "44") (name "Net-(LED9-Pad1)") (class "Default")
      (node (ref "LED9") (pin "1") (pinfunction "1_1") (pintype "passive"))
      (node (ref "R39") (pin "2") (pintype "passive"))
    )
    (net (code "45") (name "Net-(LED10-Pad1)") (class "Default")
      (node (ref "LED10") (pin "1") (pinfunction "1_1") (pintype "passive"))
      (node (ref "R48") (pin "2") (pintype "passive"))
    )
    (net (code "46") (name "Net-(LED11-Pad1)") (class "Default")
      (node (ref "LED11") (pin "1") (pinfunction "1_1") (pintype "passive"))
      (node (ref "R49") (pin "2") (pintype "passive"))
    )
    (net (code "47") (name "Net-(LED12-Pad1)") (class "Default")
      (node (ref "LED12") (pin "1") (pinfunction "1_1") (pintype "passive"))
      (node (ref "R51") (pin "2") (pintype "passive"))
    )
    (net (code "48") (name "Net-(LED13-Pad1)") (class "Default")
      (node (ref "LED13") (pin "1") (pinfunction "1_1") (pintype "passive"))
      (node (ref "R55") (pin "2") (pintype "passive"))
    )
    (net (code "49") (name "Net-(LED14-Pad1)") (class "Default")
      (node (ref "LED14") (pin "1") (pinfunction "1_1") (pintype "passive"))
      (node (ref "R56") (pin "2") (pintype "passive"))
    )
    (net (code "50") (name "Net-(Q1-BASE)") (class "Default")
      (node (ref "Q1") (pin "B") (pinfunction "BASE_B") (pintype "input"))
      (node (ref "Q31") (pin "E") (pinfunction "EMITTER_E") (pintype "passive"))
      (node (ref "R17") (pin "2") (pinfunction "2_2") (pintype "passive"))
    )
    (net (code "51") (name "Net-(Q1-COLLECTOR)") (class "Default")
      (node (ref "Q1") (pin "C") (pinfunction "COLLECTOR_C") (pintype "passive"))
      (node (ref "Q31") (pin "B") (pinfunction "BASE_B") (pintype "input"))
      (node (ref "R15") (pin "1") (pinfunction "1_1") (pintype "passive"))
      (node (ref "R16") (pin "2") (pinfunction "2_2") (pintype "passive"))
    )
    (net (code "52") (name "Net-(Q2-Pad1)") (class "Default")
      (node (ref "Q2") (pin "1") (pinfunction "1_1") (pintype "passive"))
      (node (ref "R11") (pin "1") (pinfunction "1_1") (pintype "passive"))
      (node (ref "R4") (pin "1") (pinfunction "1_1") (pintype "passive"))
    )
    (net (code "53") (name "Net-(Q3-BASE)") (class "Default")
      (node (ref "Q3") (pin "B") (pinfunction "BASE_B") (pintype "input"))
      (node (ref "R1") (pin "2") (pinfunction "2_2") (pintype "passive"))
      (node (ref "R58") (pin "2") (pinfunction "2_2") (pintype "passive"))
    )
    (net (code "54") (name "Net-(Q4-Pad1)") (class "Default")
      (node (ref "Q4") (pin "1") (pinfunction "1_1") (pintype "passive"))
      (node (ref "R53") (pin "2") (pintype "passive"))
      (node (ref "R54") (pin "2") (pintype "passive"))
    )
    (net (code "55") (name "Net-(Q4-Pad3)") (class "Default")
      (node (ref "Q4") (pin "3") (pinfunction "3_3") (pintype "passive"))
      (node (ref "R57") (pin "2") (pinfunction "2_2") (pintype "passive"))
    )
    (net (code "56") (name "Net-(Q31-COLLECTOR)") (class "Default")
      (node (ref "LED10") (pin "2") (pinfunction "2_2") (pintype "passive"))
      (node (ref "LED11") (pin "2") (pinfunction "2_2") (pintype "passive"))
      (node (ref "LED12") (pin "2") (pinfunction "2_2") (pintype "passive"))
      (node (ref "LED13") (pin "2") (pinfunction "2_2") (pintype "passive"))
      (node (ref "LED14") (pin "2") (pinfunction "2_2") (pintype "passive"))
      (node (ref "LED3") (pin "2") (pinfunction "2_2") (pintype "passive"))
      (node (ref "LED4") (pin "2") (pinfunction "2_2") (pintype "passive"))
      (node (ref "LED5") (pin "2") (pinfunction "2_2") (pintype "passive"))
      (node (ref "LED6") (pin "2") (pinfunction "2_2") (pintype "passive"))
      (node (ref "LED7") (pin "2") (pinfunction "2_2") (pintype "passive"))
      (node (ref "LED8") (pin "2") (pinfunction "2_2") (pintype "passive"))
      (node (ref "LED9") (pin "2") (pinfunction "2_2") (pintype "passive"))
      (node (ref "Q31") (pin "C") (pinfunction "COLLECTOR_C") (pintype "passive"))
    )
    (net (code "57") (name "Net-(T1-GATE)") (class "Default")
      (node (ref "R10") (pin "2") (pinfunction "2_2") (pintype "passive"))
      (node (ref "R57") (pin "1") (pinfunction "1_1") (pintype "passive"))
      (node (ref "T1") (pin "G") (pinfunction "GATE_G") (pintype "passive"))
      (node (ref "T2") (pin "G") (pinfunction "GATE_G") (pintype "passive"))
    )
    (net (code "58") (name "Net-(U6-CP1)") (class "Default")
      (node (ref "C37") (pin "1") (pinfunction "1_1") (pintype "passive"))
      (node (ref "U6") (pin "17") (pinfunction "CP1_17") (pintype "passive"))
    )
    (net (code "59") (name "Net-(U6-CP2)") (class "Default")
      (node (ref "C37") (pin "2") (pinfunction "2_2") (pintype "passive"))
      (node (ref "U6") (pin "18") (pinfunction "CP2_18") (pintype "passive"))
    )
    (net (code "60") (name "Net-(U6-VCPOUT)") (class "Default")
      (node (ref "C34") (pin "1") (pinfunction "1_1") (pintype "passive"))
      (node (ref "U6") (pin "19") (pinfunction "VCPOUT_19") (pintype "passive"))
    )
    (net (code "61") (name "Net-(U6-XTALI)") (class "Default")
      (node (ref "C38") (pin "2") (pinfunction "2_2") (pintype "passive"))
      (node (ref "U6") (pin "3") (pinfunction "XTALI_3") (pintype "passive"))
      (node (ref "X1") (pin "3") (pintype "passive"))
    )
    (net (code "62") (name "Net-(U6-XTALO)") (class "Default")
      (node (ref "C2") (pin "2") (pinfunction "2_2") (pintype "passive"))
      (node (ref "U6") (pin "2") (pinfunction "XTALO_2") (pintype "passive"))
      (node (ref "X1") (pin "1") (pintype "passive"))
    )
    (net (code "63") (name "VDD") (class "Default")
      (node (ref "C28") (pin "2") (pinfunction "2_2") (pintype "passive"))
      (node (ref "C33") (pin "2") (pinfunction "2_2") (pintype "passive"))
      (node (ref "C35") (pin "2") (pinfunction "2_2") (pintype "passive"))
      (node (ref "C36") (pin "2") (pinfunction "2_2") (pintype "passive"))
      (node (ref "C44") (pin "2") (pinfunction "2_2") (pintype "passive"))
      (node (ref "L3") (pin "1") (pinfunction "P1_1") (pintype "passive"))
      (node (ref "U6") (pin "1") (pinfunction "VCCIF_1") (pintype "passive"))
      (node (ref "U6") (pin "22") (pinfunction "VCCMCU_22") (pintype "passive"))
      (node (ref "U6") (pin "31") (pinfunction "VCCRF_31") (pintype "passive"))
    )
    (net (code "64") (name "VDD3V3") (class "Default")
      (node (ref "J3") (pin "2") (pinfunction "2_2") (pintype "passive"))
      (node (ref "J5") (pin "6") (pinfunction "6_6") (pintype "passive"))
      (node (ref "J6") (pin "6") (pinfunction "6_6") (pintype "passive"))
      (node (ref "LED1") (pin "1") (pinfunction "A_1") (pintype "passive"))
      (node (ref "LED2") (pin "1") (pinfunction "A_1") (pintype "passive"))
      (node (ref "R15") (pin "2") (pinfunction "2_2") (pintype "passive"))
      (node (ref "T2") (pin "D") (pinfunction "DRAIN_D") (pintype "passive"))
    )
    (net (code "65") (name "VDD5V") (class "Default")
      (node (ref "R27") (pin "1") (pintype "passive"))
      (node (ref "R28") (pin "1") (pintype "passive"))
      (node (ref "R30") (pin "1") (pintype "passive"))
      (node (ref "R39") (pin "1") (pintype "passive"))
      (node (ref "R47") (pin "2") (pinfunction "2_2") (pintype "passive"))
      (node (ref "R48") (pin "1") (pintype "passive"))
      (node (ref "R49") (pin "1") (pintype "passive"))
      (node (ref "R51") (pin "1") (pintype "passive"))
      (node (ref "R55") (pin "1") (pintype "passive"))
      (node (ref "R56") (pin "1") (pintype "passive"))
      (node (ref "R7") (pin "1") (pintype "passive"))
      (node (ref "R8") (pin "1") (pintype "passive"))
      (node (ref "R9") (pin "1") (pintype "passive"))
      (node (ref "T1") (pin "D") (pinfunction "DRAIN_D") (pintype "passive"))
    )
    (net (code "66") (name "unconnected-(J5-Pad7)") (class "Default")
      (node (ref "J5") (pin "7") (pinfunction "7_7") (pintype "passive"))
    )
    (net (code "67") (name "unconnected-(J5-Pad8)") (class "Default")
      (node (ref "J5") (pin "8") (pinfunction "8_8") (pintype "passive"))
    )
    (net (code "68") (name "unconnected-(U6-P32-Pad5)") (class "Default")
      (node (ref "U6") (pin "5") (pinfunction "P32_5") (pintype "passive"))
    )
    (net (code "69") (name "unconnected-(U6-P33-Pad12)") (class "Default")
      (node (ref "U6") (pin "12") (pinfunction "P33_12") (pintype "passive"))
    )
    (net (code "70") (name "unconnected-(U6-VDDSPI-Pad13)") (class "Default")
      (node (ref "U6") (pin "13") (pinfunction "VDDSPI_13") (pintype "passive"))
    )
    (net (code "71") (name "unconnected-(U6-XTAL32K-Pad9)") (class "Default")
      (node (ref "U6") (pin "9") (pinfunction "XTAL32K_9") (pintype "passive"))
    )
    (net (code "72") (name "unconnected-(UB1-Pad3)") (class "Default")
      (node (ref "UB1") (pin "3") (pinfunction "3_3") (pintype "passive"))
    )
    (net (code "73") (name "unconnected-(UB1-Pad7)") (class "Default")
      (node (ref "UB1") (pin "7") (pinfunction "7_7") (pintype "passive"))
    )
  )
)
